# SPI_LVDS_Master.net
KiCad netlist of a schematic drawn in Altium Designer
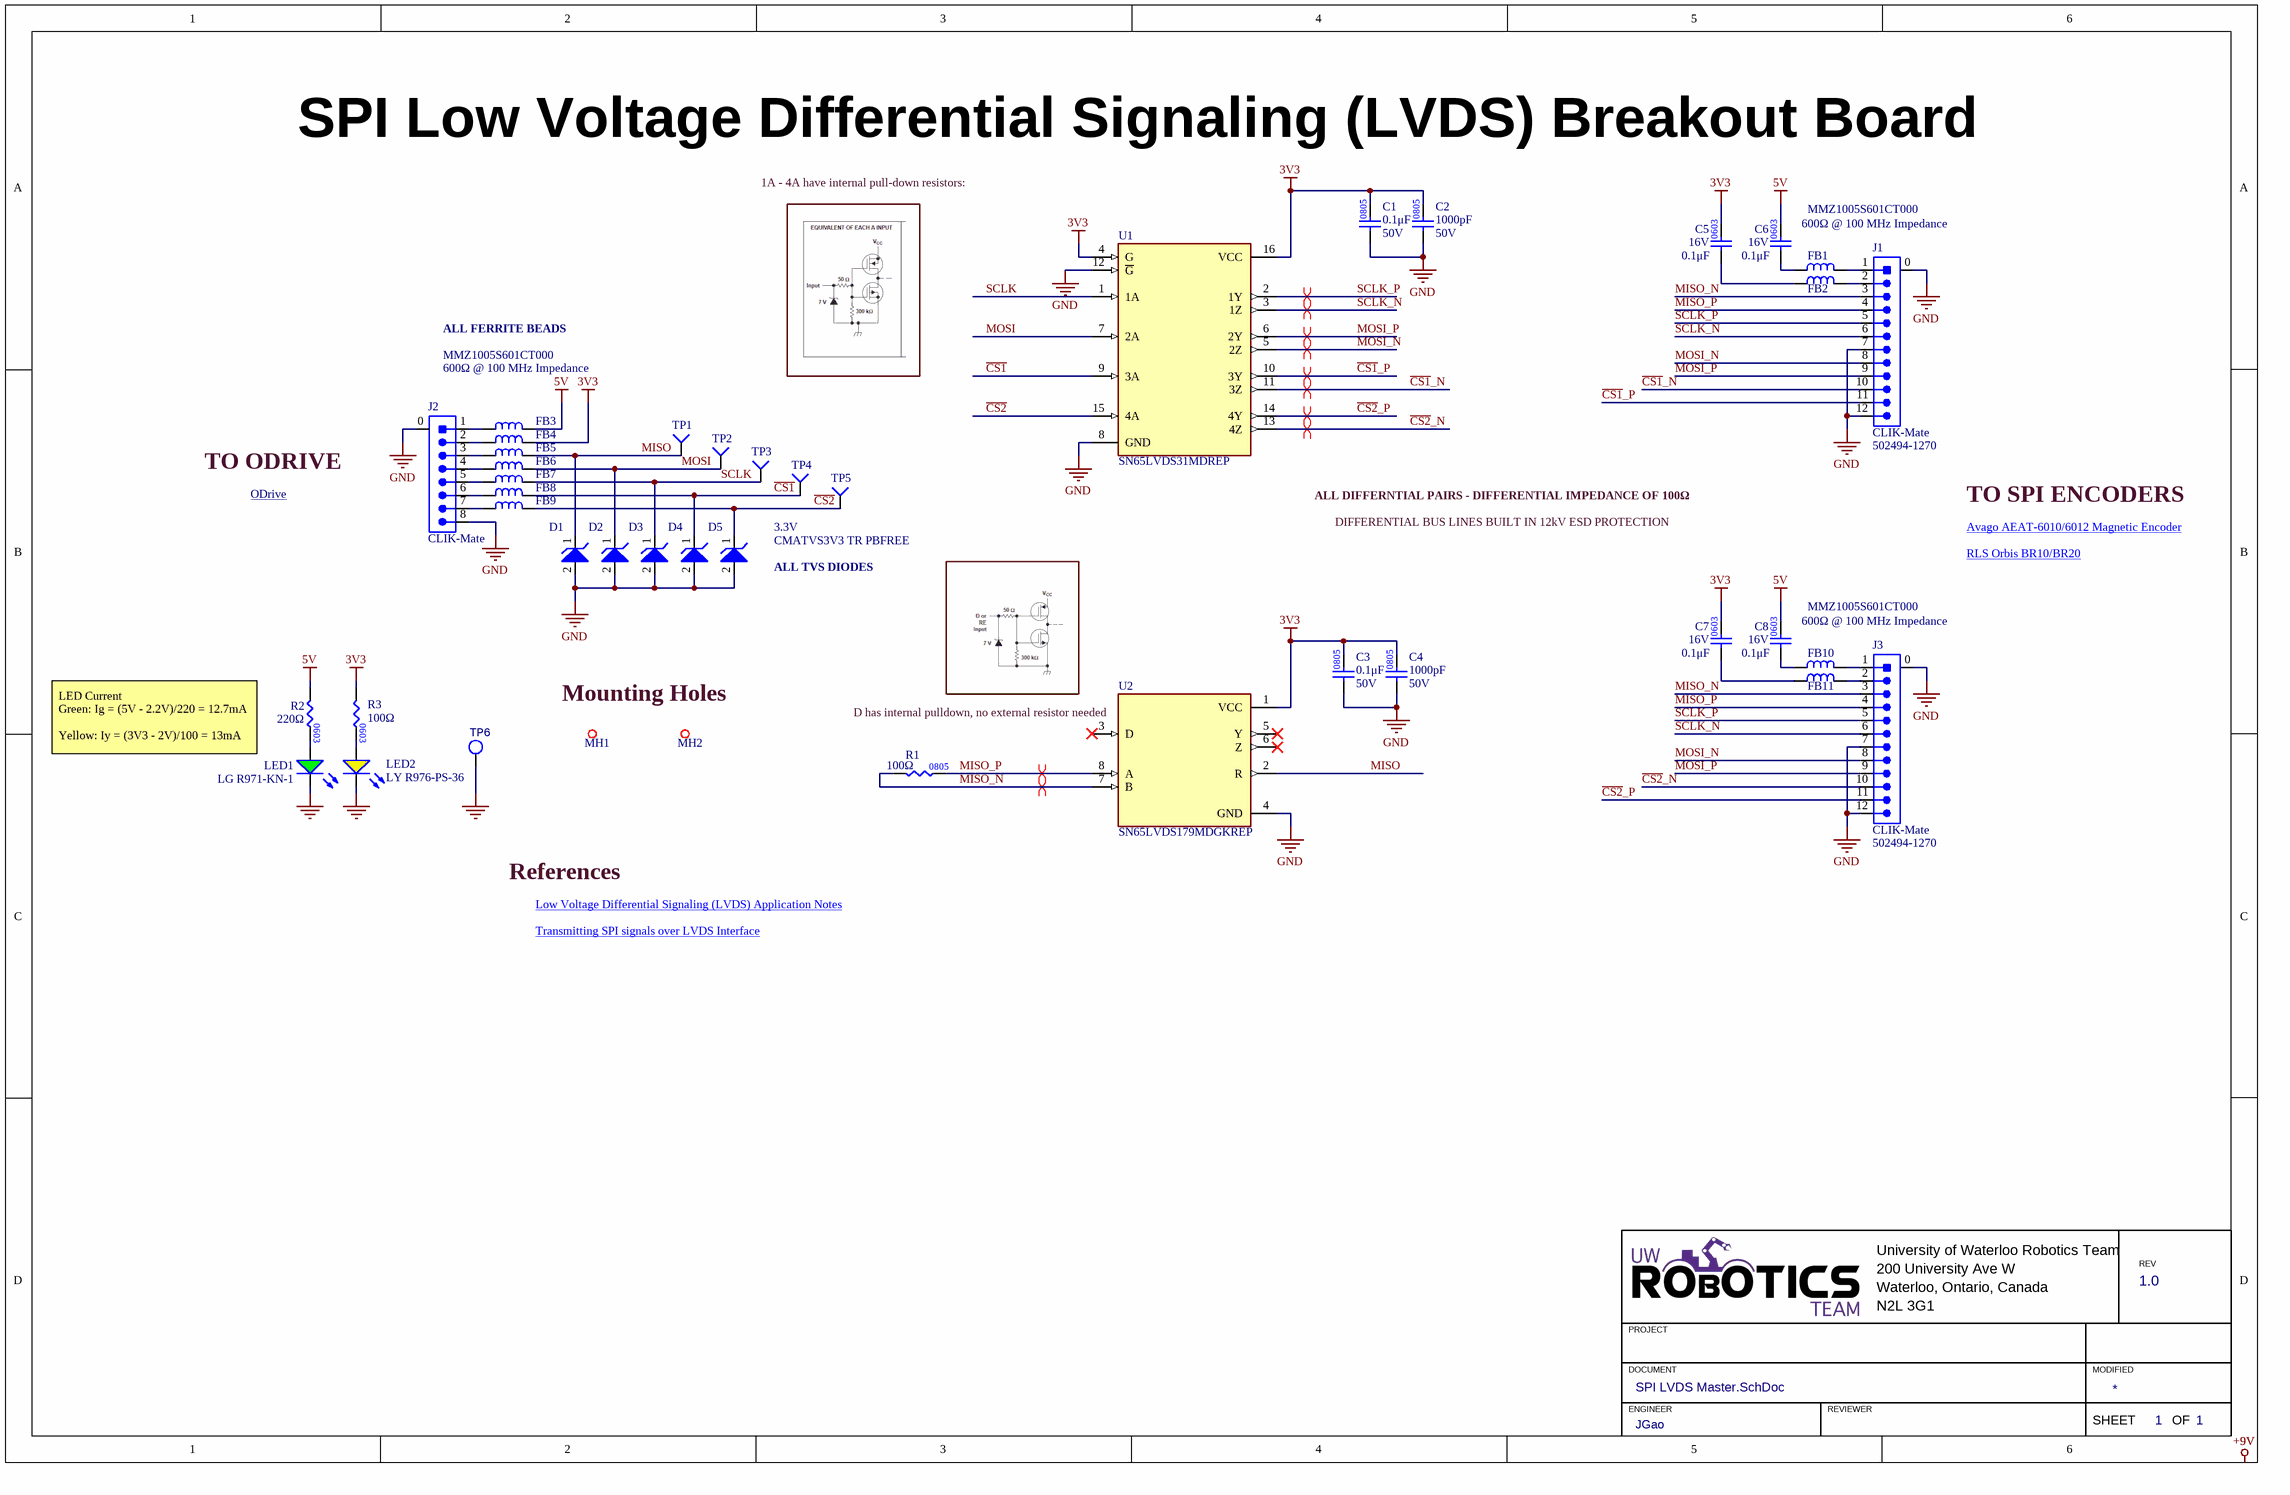
[diagram p0: SPI LVDS Master.SchDoc]

(export (version "E")
  (design (tool "Eeschema 10.0.6"))
  (components
    (comp (ref "C1")
      (value "0.1μF")
      (footprint "CAP2012")
      (description "CAP CER 0.1UF 50V X7R 0805")
      (fields
        (field (name "LCSC PART #") "C49678")
        (field (name "VOLTAGE RATING") "50V")
        (field (name "Comment") "CAP_0.1uF_50V_0805")
      )
      (libsource (lib "UWRT_Schematic_Library_2020") (part "CAP_0.1uF_50V_0805"))
    )
    (comp (ref "C2")
      (value "1000pF")
      (footprint "CAP2012")
      (description "CAP CER 1000pF 50V X7R 0805")
      (fields (field (name "VOLTAGE RATING") "50V") (field (name "Comment") "CAP_1000pF_50V_0805"))
      (libsource (lib "UWRT_Schematic_Library_2020") (part "CAP_1000pF_50V_0805"))
    )
    (comp (ref "C3")
      (value "0.1μF")
      (footprint "CAP2012")
      (description "CAP CER 0.1UF 50V X7R 0805")
      (fields
        (field (name "LCSC PART #") "C49678")
        (field (name "VOLTAGE RATING") "50V")
        (field (name "Comment") "CAP_0.1uF_50V_0805")
      )
      (libsource (lib "UWRT_Schematic_Library_2020") (part "CAP_0.1uF_50V_0805"))
    )
    (comp (ref "C4")
      (value "1000pF")
      (footprint "CAP2012")
      (description "CAP CER 1000pF 50V X7R 0805")
      (fields (field (name "VOLTAGE RATING") "50V") (field (name "Comment") "CAP_1000pF_50V_0805"))
      (libsource (lib "UWRT_Schematic_Library_2020") (part "CAP_1000pF_50V_0805"))
    )
    (comp (ref "C5")
      (value "0.1μF")
      (footprint "CAP0603")
      (description "CAP CER 0.1UF 16V X7R 0603")
      (fields (field (name "VOLTAGE RATING") "16V") (field (name "Comment") "CAP_0.1uF_16V_0603"))
      (libsource (lib "UWRT_Schematic_Library_2020") (part "CAP_0.1uF_16V_0603"))
    )
    (comp (ref "C6")
      (value "0.1μF")
      (footprint "CAP0603")
      (description "CAP CER 0.1UF 16V X7R 0603")
      (fields (field (name "VOLTAGE RATING") "16V") (field (name "Comment") "CAP_0.1uF_16V_0603"))
      (libsource (lib "UWRT_Schematic_Library_2020") (part "CAP_0.1uF_16V_0603"))
    )
    (comp (ref "C7")
      (value "0.1μF")
      (footprint "CAP0603")
      (description "CAP CER 0.1UF 16V X7R 0603")
      (fields (field (name "VOLTAGE RATING") "16V") (field (name "Comment") "CAP_0.1uF_16V_0603"))
      (libsource (lib "UWRT_Schematic_Library_2020") (part "CAP_0.1uF_16V_0603"))
    )
    (comp (ref "C8")
      (value "0.1μF")
      (footprint "CAP0603")
      (description "CAP CER 0.1UF 16V X7R 0603")
      (fields (field (name "VOLTAGE RATING") "16V") (field (name "Comment") "CAP_0.1uF_16V_0603"))
      (libsource (lib "UWRT_Schematic_Library_2020") (part "CAP_0.1uF_16V_0603"))
    )
    (comp (ref "D1")
      (value "TVS_DIODE_UNIDIR_3.3V_7A")
      (footprint "SOD-923")
      (description "TVS DIODE 3.3VWM 11VC SOD923")
      (fields
        (field (name "VOLTAGE - REVERSE STANDOFF (TYP)") "3.3V")
        (field (name "MANUFACTURER PART NUMBER 1") "CMATVS3V3 TR PBFREE")
      )
      (libsource (lib "UWRT_Schematic_Library_2020") (part "TVS_DIODE_UNIDIR_3.3V_7A"))
    )
    (comp (ref "D2")
      (value "TVS_DIODE_UNIDIR_3.3V_7A")
      (footprint "SOD-923")
      (description "TVS DIODE 3.3VWM 11VC SOD923")
      (libsource (lib "UWRT_Schematic_Library_2020") (part "TVS_DIODE_UNIDIR_3.3V_7A"))
    )
    (comp (ref "D3")
      (value "TVS_DIODE_UNIDIR_3.3V_7A")
      (footprint "SOD-923")
      (description "TVS DIODE 3.3VWM 11VC SOD923")
      (libsource (lib "UWRT_Schematic_Library_2020") (part "TVS_DIODE_UNIDIR_3.3V_7A"))
    )
    (comp (ref "D4")
      (value "TVS_DIODE_UNIDIR_3.3V_7A")
      (footprint "SOD-923")
      (description "TVS DIODE 3.3VWM 11VC SOD923")
      (libsource (lib "UWRT_Schematic_Library_2020") (part "TVS_DIODE_UNIDIR_3.3V_7A"))
    )
    (comp (ref "D5")
      (value "TVS_DIODE_UNIDIR_3.3V_7A")
      (footprint "SOD-923")
      (description "TVS DIODE 3.3VWM 11VC SOD923")
      (libsource (lib "UWRT_Schematic_Library_2020") (part "TVS_DIODE_UNIDIR_3.3V_7A"))
    )
    (comp (ref "FB1")
      (value "FERRITE_BEAD_600OHM_0402")
      (footprint "RES0402")
      (description "FIXED IND 1UH 3.8A 33 MOHM SMD")
      (fields (field (name "MANUFACTURER PART NUMBER 1") "MMZ1005S601CT000"))
      (libsource (lib "") (part "FERRITE_BEAD_600OHM_0402_1"))
    )
    (comp (ref "FB2")
      (value "FERRITE_BEAD_600OHM_0402")
      (footprint "RES0402")
      (description "FIXED IND 1UH 3.8A 33 MOHM SMD")
      (libsource (lib "") (part "FERRITE_BEAD_600OHM_0402_1"))
    )
    (comp (ref "FB3")
      (value "FERRITE_BEAD_600OHM_0402")
      (footprint "RES0402")
      (description "FIXED IND 1UH 3.8A 33 MOHM SMD")
      (fields (field (name "MANUFACTURER PART NUMBER 1") "MMZ1005S601CT000"))
      (libsource (lib "UWRT_Schematic_Library_2020") (part "FERRITE_BEAD_600OHM_0402"))
    )
    (comp (ref "FB4")
      (value "FERRITE_BEAD_600OHM_0402")
      (footprint "RES0402")
      (description "FIXED IND 1UH 3.8A 33 MOHM SMD")
      (libsource (lib "UWRT_Schematic_Library_2020") (part "FERRITE_BEAD_600OHM_0402"))
    )
    (comp (ref "FB5")
      (value "FERRITE_BEAD_600OHM_0402")
      (footprint "RES0402")
      (description "FIXED IND 1UH 3.8A 33 MOHM SMD")
      (libsource (lib "UWRT_Schematic_Library_2020") (part "FERRITE_BEAD_600OHM_0402"))
    )
    (comp (ref "FB6")
      (value "FERRITE_BEAD_600OHM_0402")
      (footprint "RES0402")
      (description "FIXED IND 1UH 3.8A 33 MOHM SMD")
      (libsource (lib "UWRT_Schematic_Library_2020") (part "FERRITE_BEAD_600OHM_0402"))
    )
    (comp (ref "FB7")
      (value "FERRITE_BEAD_600OHM_0402")
      (footprint "RES0402")
      (description "FIXED IND 1UH 3.8A 33 MOHM SMD")
      (libsource (lib "UWRT_Schematic_Library_2020") (part "FERRITE_BEAD_600OHM_0402"))
    )
    (comp (ref "FB8")
      (value "FERRITE_BEAD_600OHM_0402")
      (footprint "RES0402")
      (description "FIXED IND 1UH 3.8A 33 MOHM SMD")
      (libsource (lib "UWRT_Schematic_Library_2020") (part "FERRITE_BEAD_600OHM_0402"))
    )
    (comp (ref "FB9")
      (value "FERRITE_BEAD_600OHM_0402")
      (footprint "RES0402")
      (description "FIXED IND 1UH 3.8A 33 MOHM SMD")
      (libsource (lib "UWRT_Schematic_Library_2020") (part "FERRITE_BEAD_600OHM_0402"))
    )
    (comp (ref "FB10")
      (value "FERRITE_BEAD_600OHM_0402")
      (footprint "RES0402")
      (description "FIXED IND 1UH 3.8A 33 MOHM SMD")
      (fields (field (name "MANUFACTURER PART NUMBER 1") "MMZ1005S601CT000"))
      (libsource (lib "") (part "FERRITE_BEAD_600OHM_0402_1"))
    )
    (comp (ref "FB11")
      (value "FERRITE_BEAD_600OHM_0402")
      (footprint "RES0402")
      (description "FIXED IND 1UH 3.8A 33 MOHM SMD")
      (libsource (lib "") (part "FERRITE_BEAD_600OHM_0402_1"))
    )
    (comp (ref "J1")
      (value "CON_12M_SM_RA_2mm")
      (footprint "MOLEX-5024941270")
      (description "2.00mm Pitch CLIK-Mate Wire-to-Board PCB Receptacle, Single Row, Right-Angle, 12 Circuits")
      (fields
        (field (name "MANUFACTURER") "Molex")
        (field (name "MANUFACTURER PART NUMBER") "502494-1270")
        (field (name "FAMILY") "CLIK-Mate")
        (field (name "SUPPLIER PART NUMBER 1") "502494-1270")
      )
      (libsource (lib "UWRT_Schematic_Library_2020") (part "CON_12M_SM_RA_2mm"))
    )
    (comp (ref "J2")
      (value "CON_8M_SM_RA")
      (footprint "MOLEX-5025850870")
      (description "CONN HEADER SMD RIGHT ANGLE 1.5 MM PITCH")
      (fields (field (name "FAMILY") "CLIK-Mate"))
      (libsource (lib "UWRT_Schematic_Library_2020") (part "CON_8M_SM_RA"))
    )
    (comp (ref "J3")
      (value "CON_12M_SM_RA_2mm")
      (footprint "MOLEX-5024941270")
      (description "2.00mm Pitch CLIK-Mate Wire-to-Board PCB Receptacle, Single Row, Right-Angle, 12 Circuits")
      (fields
        (field (name "MANUFACTURER") "Molex")
        (field (name "MANUFACTURER PART NUMBER") "502494-1270")
        (field (name "FAMILY") "CLIK-Mate")
        (field (name "SUPPLIER PART NUMBER 1") "502494-1270")
      )
      (libsource (lib "UWRT_Schematic_Library_2020") (part "CON_12M_SM_RA_2mm"))
    )
    (comp (ref "LED1")
      (value "LED_GREEN")
      (footprint "LED_0805_GREEN")
      (description "LED GREEN DIFFUSED 0805 SMD")
      (fields (field (name "MANUFACTURER PART NUMBER 1") "LG R971-KN-1"))
      (libsource (lib "UWRT_Schematic_Library_2020") (part "LED_GREEN"))
    )
    (comp (ref "LED2")
      (value "LED_YELLOW")
      (footprint "LED_0805_YELLOW")
      (description "LED YELLOW DIFFUSED 0805 SMD")
      (fields (field (name "MANUFACTURER PART NUMBER 1") "LY R976-PS-36"))
      (libsource (lib "UWRT_Schematic_Library_2020") (part "LED_YELLOW"))
    )
    (comp (ref "MH1")
      (value "MOUNTING_HOLE_M3")
      (footprint "MOUNTING_HOLE_3mm")
      (libsource (lib "UWRT_Schematic_Library_2020") (part "MOUNTING_HOLE_M3"))
    )
    (comp (ref "MH2")
      (value "MOUNTING_HOLE_M3")
      (footprint "MOUNTING_HOLE_3mm")
      (libsource (lib "UWRT_Schematic_Library_2020") (part "MOUNTING_HOLE_M3"))
    )
    (comp (ref "R1")
      (value "100Ω")
      (footprint "RES0805")
      (description "RES 100 OHM 1% 1/8W 0805")
      (fields (field (name "LCSC PART #") "C1790") (field (name "Comment") "RES_100Ω_0805_1%"))
      (libsource (lib "UWRT_Schematic_Library_2020") (part "RES_100Ω_0805_1%"))
    )
    (comp (ref "R2")
      (value "220Ω")
      (footprint "RES0603")
      (description "RES 220 OHM 5% 1/10W 0603")
      (fields (field (name "Comment") "RES_220Ω_0603_5%"))
      (libsource (lib "UWRT_Schematic_Library_2020") (part "RES_220Ω_0603_5%"))
    )
    (comp (ref "R3")
      (value "100Ω")
      (footprint "RES0603")
      (description "RES 100 OHM 1% 1/10W 0603")
      (fields (field (name "Comment") "RES_100Ω_0603_1%"))
      (libsource (lib "UWRT_Schematic_Library_2020") (part "RES_100Ω_0603_1%"))
    )
    (comp (ref "TP1")
      (value "TESTPOINT_1MM_SQUARE")
      (footprint "TESTPOINT_SQUARE_1MM")
      (description "TESTPOINT 1MM SQUARE")
      (libsource (lib "UWRT_Schematic_Library_2020") (part "TESTPOINT_1MM_SQUARE"))
    )
    (comp (ref "TP2")
      (value "TESTPOINT_1MM_SQUARE")
      (footprint "TESTPOINT_SQUARE_1MM")
      (description "TESTPOINT 1MM SQUARE")
      (libsource (lib "UWRT_Schematic_Library_2020") (part "TESTPOINT_1MM_SQUARE"))
    )
    (comp (ref "TP3")
      (value "TESTPOINT_1MM_SQUARE")
      (footprint "TESTPOINT_SQUARE_1MM")
      (description "TESTPOINT 1MM SQUARE")
      (libsource (lib "UWRT_Schematic_Library_2020") (part "TESTPOINT_1MM_SQUARE"))
    )
    (comp (ref "TP4")
      (value "TESTPOINT_1MM_SQUARE")
      (footprint "TESTPOINT_SQUARE_1MM")
      (description "TESTPOINT 1MM SQUARE")
      (libsource (lib "UWRT_Schematic_Library_2020") (part "TESTPOINT_1MM_SQUARE"))
    )
    (comp (ref "TP5")
      (value "TESTPOINT_1MM_SQUARE")
      (footprint "TESTPOINT_SQUARE_1MM")
      (description "TESTPOINT 1MM SQUARE")
      (libsource (lib "UWRT_Schematic_Library_2020") (part "TESTPOINT_1MM_SQUARE"))
    )
    (comp (ref "TP6")
      (value "TESTPOINT_LOOP")
      (footprint "TESTPOINT_LOOP")
      (description "TESTPOINT THRUHOLE")
      (libsource (lib "UWRT_Schematic_Library_2020") (part "TESTPOINT_LOOP"))
    )
    (comp (ref "U1")
      (value "SN65LVDS31MDREP")
      (footprint "SOIC127P600X175-16N")
      (description "IC DRIVER 4/0 16SOIC")
      (libsource (lib "UWRT_Schematic_Library_2020") (part "SN65LVDS31MDREP"))
    )
    (comp (ref "U2")
      (value "SN65LVDS179MDGKREP")
      (footprint "SOP65P490X110-8N")
      (description "Enhanced Product High-Speed Differential Line Drivers And Receivers 8-VSSOP -55 to 125")
      (fields (field (name "MF") "Texas Instruments") (field (name "DIGI-KEY_PART_NUMBER") "296-22243-1-ND"))
      (libsource (lib "UWRT_Schematic_Library_2020") (part "SN65LVDS179MDGKREP"))
    )
  )
  (nets
    (net (code "2") (name "/MISO") (class "Default")
      (node (ref "D1") (pin "1") (pinfunction "1_1") (pintype "passive"))
      (node (ref "FB5") (pin "2") (pinfunction "2_2") (pintype "passive"))
      (node (ref "TP1") (pin "1") (pinfunction "=value_1") (pintype "passive"))
      (node (ref "U2") (pin "2") (pinfunction "R_2") (pintype "output"))
    )
    (net (code "3") (name "/MISO_N") (class "Default")
      (node (ref "J1") (pin "3") (pinfunction "3_3") (pintype "passive"))
      (node (ref "J3") (pin "3") (pinfunction "3_3") (pintype "passive"))
      (node (ref "R1") (pin "1") (pinfunction "1_1") (pintype "passive"))
      (node (ref "U2") (pin "7") (pinfunction "B_7") (pintype "input"))
    )
    (net (code "4") (name "/MISO_P") (class "Default")
      (node (ref "J1") (pin "4") (pinfunction "4_4") (pintype "passive"))
      (node (ref "J3") (pin "4") (pinfunction "4_4") (pintype "passive"))
      (node (ref "R1") (pin "2") (pinfunction "2_2") (pintype "passive"))
      (node (ref "U2") (pin "8") (pinfunction "A_8") (pintype "input"))
    )
    (net (code "5") (name "/MOSI") (class "Default")
      (node (ref "D2") (pin "1") (pinfunction "1_1") (pintype "passive"))
      (node (ref "FB6") (pin "2") (pinfunction "2_2") (pintype "passive"))
      (node (ref "TP2") (pin "1") (pinfunction "=value_1") (pintype "passive"))
      (node (ref "U1") (pin "7") (pinfunction "2A_7") (pintype "input"))
    )
    (net (code "6") (name "/MOSI_N") (class "Default")
      (node (ref "J1") (pin "8") (pinfunction "6_8") (pintype "passive"))
      (node (ref "J3") (pin "8") (pinfunction "6_8") (pintype "passive"))
      (node (ref "U1") (pin "5") (pinfunction "2Z_5") (pintype "output"))
    )
    (net (code "7") (name "/MOSI_P") (class "Default")
      (node (ref "J1") (pin "9") (pinfunction "9_9") (pintype "passive"))
      (node (ref "J3") (pin "9") (pinfunction "9_9") (pintype "passive"))
      (node (ref "U1") (pin "6") (pinfunction "2Y_6") (pintype "output"))
    )
    (net (code "8") (name "/SCLK") (class "Default")
      (node (ref "D3") (pin "1") (pinfunction "1_1") (pintype "passive"))
      (node (ref "FB7") (pin "2") (pinfunction "2_2") (pintype "passive"))
      (node (ref "TP3") (pin "1") (pinfunction "=value_1") (pintype "passive"))
      (node (ref "U1") (pin "1") (pinfunction "1A_1") (pintype "input"))
    )
    (net (code "9") (name "/SCLK_N") (class "Default")
      (node (ref "J1") (pin "6") (pinfunction "6_6") (pintype "passive"))
      (node (ref "J3") (pin "6") (pinfunction "6_6") (pintype "passive"))
      (node (ref "U1") (pin "3") (pinfunction "1Z_3") (pintype "output"))
    )
    (net (code "10") (name "/SCLK_P") (class "Default")
      (node (ref "J1") (pin "5") (pinfunction "5_5") (pintype "passive"))
      (node (ref "J3") (pin "5") (pinfunction "5_5") (pintype "passive"))
      (node (ref "U1") (pin "2") (pinfunction "1Y_2") (pintype "output"))
    )
    (net (code "11") (name "/~{CS1}") (class "Default")
      (node (ref "D4") (pin "1") (pinfunction "1_1") (pintype "passive"))
      (node (ref "FB8") (pin "2") (pinfunction "2_2") (pintype "passive"))
      (node (ref "TP4") (pin "1") (pinfunction "=value_1") (pintype "passive"))
      (node (ref "U1") (pin "9") (pinfunction "3A_9") (pintype "input"))
    )
    (net (code "12") (name "/~{CS1}_N") (class "Default")
      (node (ref "J1") (pin "10") (pinfunction "10_10") (pintype "passive"))
      (node (ref "U1") (pin "11") (pinfunction "3Z_11") (pintype "output"))
    )
    (net (code "13") (name "/~{CS1}_P") (class "Default")
      (node (ref "J1") (pin "11") (pinfunction "11_11") (pintype "passive"))
      (node (ref "U1") (pin "10") (pinfunction "3Y_10") (pintype "output"))
    )
    (net (code "14") (name "/~{CS2}") (class "Default")
      (node (ref "D5") (pin "1") (pinfunction "1_1") (pintype "passive"))
      (node (ref "FB9") (pin "2") (pinfunction "2_2") (pintype "passive"))
      (node (ref "TP5") (pin "1") (pinfunction "=value_1") (pintype "passive"))
      (node (ref "U1") (pin "15") (pinfunction "4A_15") (pintype "input"))
    )
    (net (code "15") (name "/~{CS2}_N") (class "Default")
      (node (ref "J3") (pin "10") (pinfunction "10_10") (pintype "passive"))
      (node (ref "U1") (pin "13") (pinfunction "4Z_13") (pintype "output"))
    )
    (net (code "16") (name "/~{CS2}_P") (class "Default")
      (node (ref "J3") (pin "11") (pinfunction "11_11") (pintype "passive"))
      (node (ref "U1") (pin "14") (pinfunction "4Y_14") (pintype "output"))
    )
    (net (code "17") (name "3V3") (class "Default")
      (node (ref "C1") (pin "2") (pinfunction "2_2") (pintype "passive"))
      (node (ref "C2") (pin "2") (pinfunction "2_2") (pintype "passive"))
      (node (ref "C3") (pin "2") (pinfunction "2_2") (pintype "passive"))
      (node (ref "C4") (pin "2") (pinfunction "2_2") (pintype "passive"))
      (node (ref "C5") (pin "2") (pinfunction "2_2") (pintype "passive"))
      (node (ref "C7") (pin "2") (pinfunction "2_2") (pintype "passive"))
      (node (ref "FB4") (pin "2") (pinfunction "2_2") (pintype "passive"))
      (node (ref "R3") (pin "1") (pinfunction "1_1") (pintype "passive"))
      (node (ref "U1") (pin "16") (pinfunction "VCC_16") (pintype "power_in"))
      (node (ref "U1") (pin "4") (pinfunction "G_4") (pintype "input"))
      (node (ref "U2") (pin "1") (pinfunction "VCC_1") (pintype "power_in"))
    )
    (net (code "18") (name "5V") (class "Default")
      (node (ref "C6") (pin "2") (pinfunction "2_2") (pintype "passive"))
      (node (ref "C8") (pin "2") (pinfunction "2_2") (pintype "passive"))
      (node (ref "FB3") (pin "2") (pinfunction "2_2") (pintype "passive"))
      (node (ref "R2") (pin "1") (pinfunction "1_1") (pintype "passive"))
    )
    (net (code "19") (name "GND") (class "Default")
      (node (ref "C1") (pin "1") (pinfunction "1_1") (pintype "passive"))
      (node (ref "C2") (pin "1") (pinfunction "1_1") (pintype "passive"))
      (node (ref "C3") (pin "1") (pinfunction "1_1") (pintype "passive"))
      (node (ref "C4") (pin "1") (pinfunction "1_1") (pintype "passive"))
      (node (ref "D1") (pin "2") (pinfunction "2_2") (pintype "passive"))
      (node (ref "D2") (pin "2") (pinfunction "2_2") (pintype "passive"))
      (node (ref "D3") (pin "2") (pinfunction "2_2") (pintype "passive"))
      (node (ref "D4") (pin "2") (pinfunction "2_2") (pintype "passive"))
      (node (ref "D5") (pin "2") (pinfunction "2_2") (pintype "passive"))
      (node (ref "J1") (pin "0") (pinfunction "0_0") (pintype "passive"))
      (node (ref "J1") (pin "12") (pinfunction "12_12") (pintype "passive"))
      (node (ref "J1") (pin "7") (pinfunction "6_7") (pintype "passive"))
      (node (ref "J2") (pin "0") (pinfunction "0_0") (pintype "passive"))
      (node (ref "J2") (pin "8") (pinfunction "6_8") (pintype "passive"))
      (node (ref "J3") (pin "0") (pinfunction "0_0") (pintype "passive"))
      (node (ref "J3") (pin "12") (pinfunction "12_12") (pintype "passive"))
      (node (ref "J3") (pin "7") (pinfunction "6_7") (pintype "passive"))
      (node (ref "LED1") (pin "2") (pinfunction "K_2") (pintype "passive"))
      (node (ref "LED2") (pin "2") (pinfunction "K_2") (pintype "passive"))
      (node (ref "TP6") (pin "1") (pintype "passive"))
      (node (ref "U1") (pin "12") (pinfunction "~{G}_12") (pintype "input"))
      (node (ref "U1") (pin "8") (pinfunction "GND_8") (pintype "power_in"))
      (node (ref "U2") (pin "4") (pinfunction "GND_4") (pintype "power_in"))
    )
    (net (code "20") (name "Net-(C5-Pad1)") (class "Default")
      (node (ref "C5") (pin "1") (pinfunction "1_1") (pintype "passive"))
      (node (ref "FB2") (pin "2") (pinfunction "2_2") (pintype "passive"))
    )
    (net (code "21") (name "Net-(C6-Pad1)") (class "Default")
      (node (ref "C6") (pin "1") (pinfunction "1_1") (pintype "passive"))
      (node (ref "FB1") (pin "2") (pinfunction "2_2") (pintype "passive"))
    )
    (net (code "22") (name "Net-(C7-Pad1)") (class "Default")
      (node (ref "C7") (pin "1") (pinfunction "1_1") (pintype "passive"))
      (node (ref "FB11") (pin "2") (pinfunction "2_2") (pintype "passive"))
    )
    (net (code "23") (name "Net-(C8-Pad1)") (class "Default")
      (node (ref "C8") (pin "1") (pinfunction "1_1") (pintype "passive"))
      (node (ref "FB10") (pin "2") (pinfunction "2_2") (pintype "passive"))
    )
    (net (code "24") (name "Net-(FB1-Pad1)") (class "Default")
      (node (ref "FB1") (pin "1") (pinfunction "1_1") (pintype "passive"))
      (node (ref "J1") (pin "1") (pinfunction "1_1") (pintype "passive"))
    )
    (net (code "25") (name "Net-(FB2-Pad1)") (class "Default")
      (node (ref "FB2") (pin "1") (pinfunction "1_1") (pintype "passive"))
      (node (ref "J1") (pin "2") (pinfunction "2_2") (pintype "passive"))
    )
    (net (code "26") (name "Net-(FB3-Pad1)") (class "Default")
      (node (ref "FB3") (pin "1") (pinfunction "1_1") (pintype "passive"))
      (node (ref "J2") (pin "1") (pinfunction "1_1") (pintype "passive"))
    )
    (net (code "27") (name "Net-(FB4-Pad1)") (class "Default")
      (node (ref "FB4") (pin "1") (pinfunction "1_1") (pintype "passive"))
      (node (ref "J2") (pin "2") (pinfunction "2_2") (pintype "passive"))
    )
    (net (code "28") (name "Net-(FB5-Pad1)") (class "Default")
      (node (ref "FB5") (pin "1") (pinfunction "1_1") (pintype "passive"))
      (node (ref "J2") (pin "3") (pinfunction "3_3") (pintype "passive"))
    )
    (net (code "29") (name "Net-(FB6-Pad1)") (class "Default")
      (node (ref "FB6") (pin "1") (pinfunction "1_1") (pintype "passive"))
      (node (ref "J2") (pin "4") (pinfunction "4_4") (pintype "passive"))
    )
    (net (code "30") (name "Net-(FB7-Pad1)") (class "Default")
      (node (ref "FB7") (pin "1") (pinfunction "1_1") (pintype "passive"))
      (node (ref "J2") (pin "5") (pinfunction "5_5") (pintype "passive"))
    )
    (net (code "31") (name "Net-(FB8-Pad1)") (class "Default")
      (node (ref "FB8") (pin "1") (pinfunction "1_1") (pintype "passive"))
      (node (ref "J2") (pin "6") (pinfunction "6_6") (pintype "passive"))
    )
    (net (code "32") (name "Net-(FB9-Pad1)") (class "Default")
      (node (ref "FB9") (pin "1") (pinfunction "1_1") (pintype "passive"))
      (node (ref "J2") (pin "7") (pinfunction "6_7") (pintype "passive"))
    )
    (net (code "33") (name "Net-(FB10-Pad1)") (class "Default")
      (node (ref "FB10") (pin "1") (pinfunction "1_1") (pintype "passive"))
      (node (ref "J3") (pin "1") (pinfunction "1_1") (pintype "passive"))
    )
    (net (code "34") (name "Net-(FB11-Pad1)") (class "Default")
      (node (ref "FB11") (pin "1") (pinfunction "1_1") (pintype "passive"))
      (node (ref "J3") (pin "2") (pinfunction "2_2") (pintype "passive"))
    )
    (net (code "35") (name "Net-(LED1-A)") (class "Default")
      (node (ref "LED1") (pin "1") (pinfunction "A_1") (pintype "passive"))
      (node (ref "R2") (pin "2") (pinfunction "2_2") (pintype "passive"))
    )
    (net (code "36") (name "Net-(LED2-A)") (class "Default")
      (node (ref "LED2") (pin "1") (pinfunction "A_1") (pintype "passive"))
      (node (ref "R3") (pin "2") (pinfunction "2_2") (pintype "passive"))
    )
    (net (code "37") (name "unconnected-(U2-D-Pad3)") (class "Default")
      (node (ref "U2") (pin "3") (pinfunction "D_3") (pintype "input+no_connect"))
    )
    (net (code "38") (name "unconnected-(U2-Y-Pad5)") (class "Default")
      (node (ref "U2") (pin "5") (pinfunction "Y_5") (pintype "output+no_connect"))
    )
    (net (code "39") (name "unconnected-(U2-Z-Pad6)") (class "Default")
      (node (ref "U2") (pin "6") (pinfunction "Z_6") (pintype "output+no_connect"))
    )
  )
)
